# Valve_Board.net
KiCad netlist of a schematic drawn in EAGLE
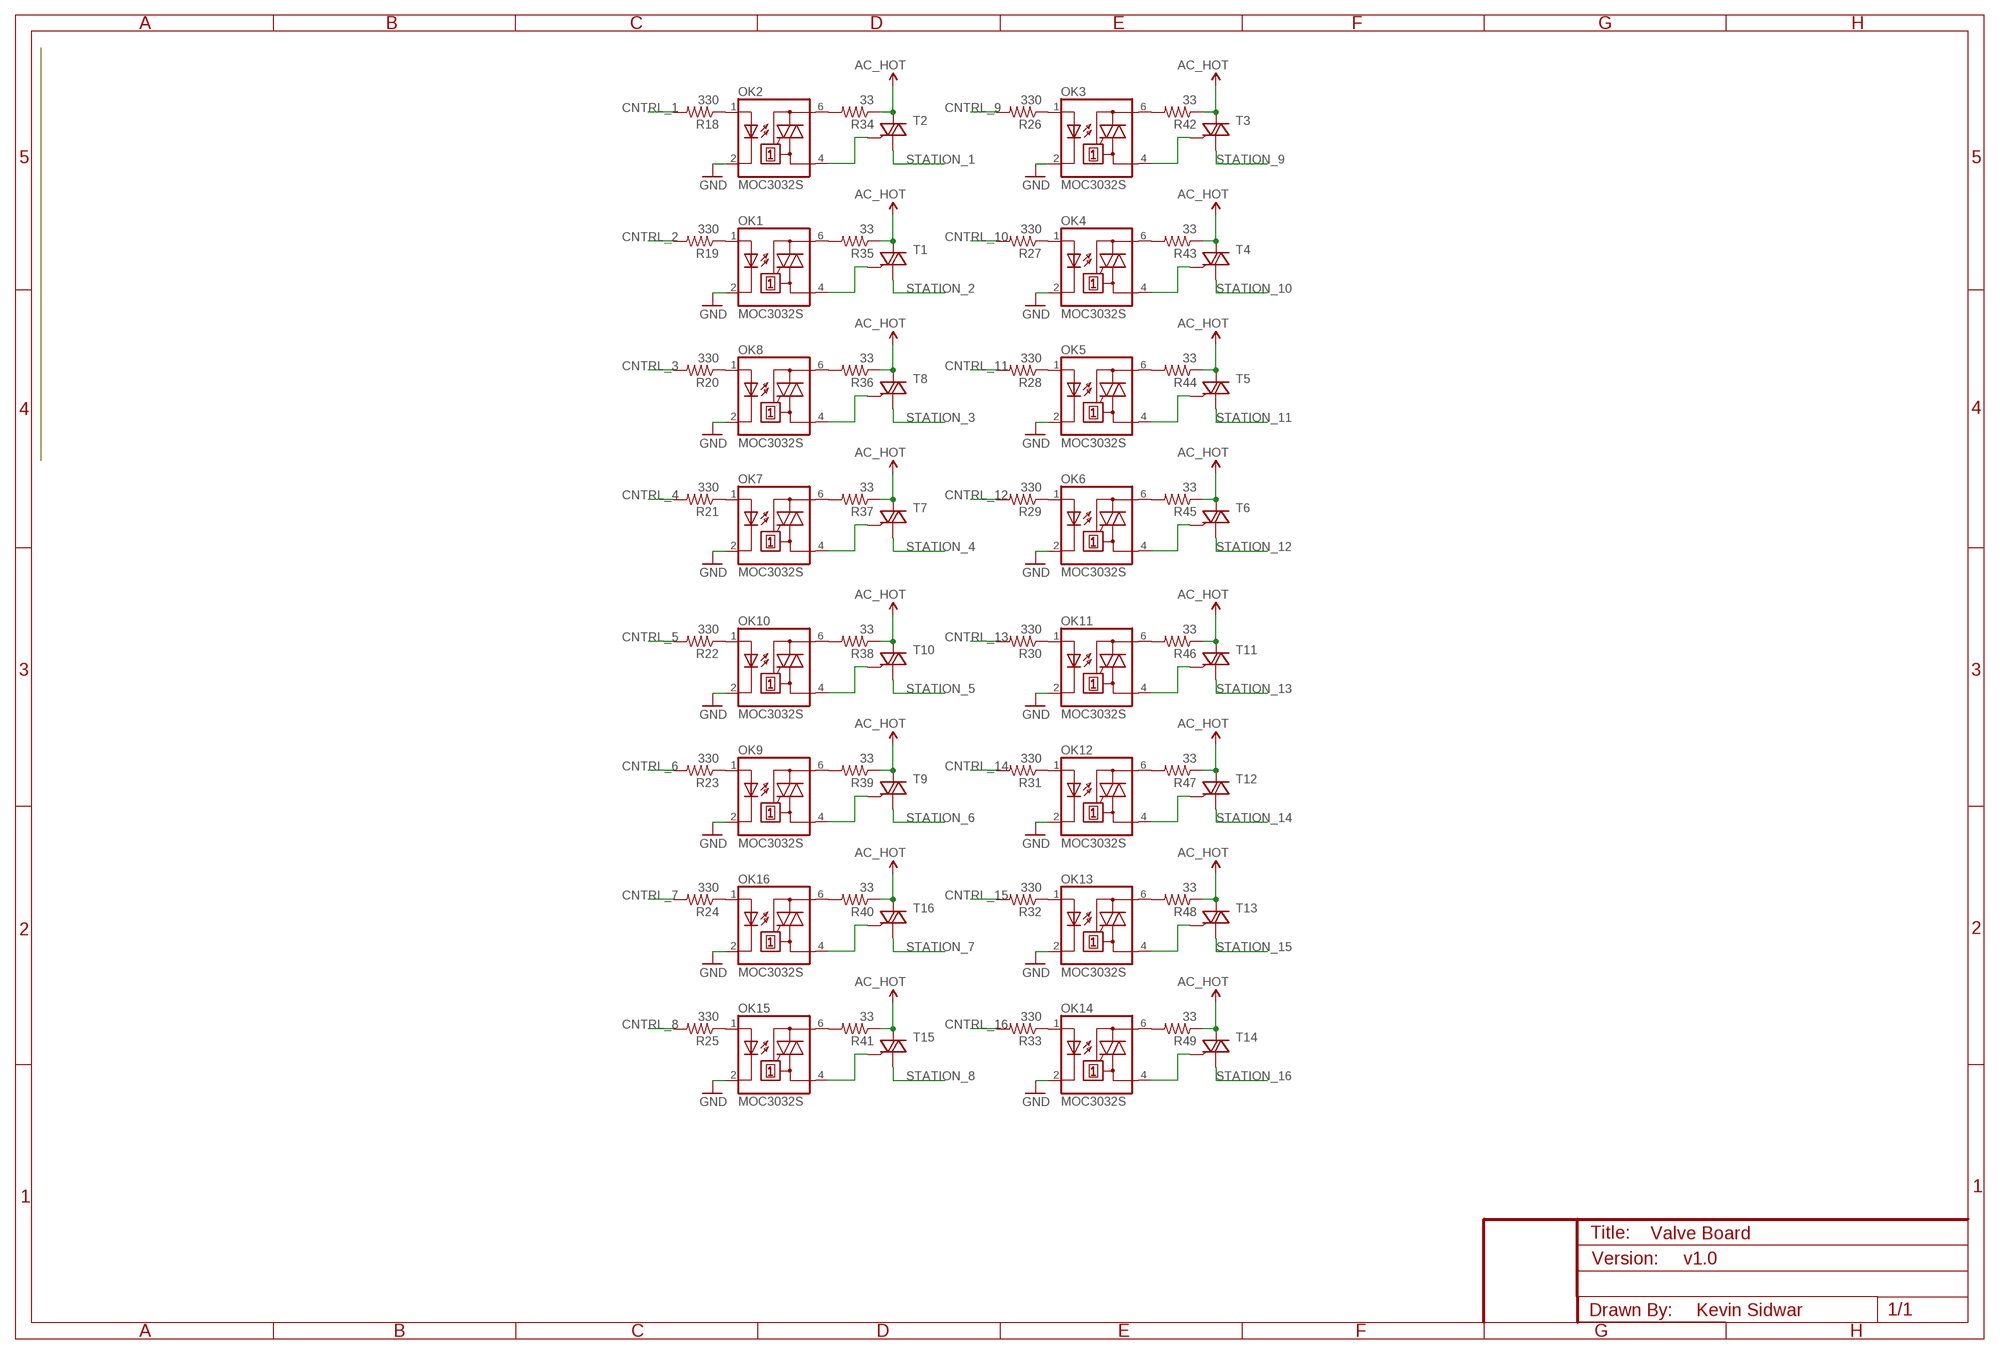
[diagram p0: schematic, sheet 1]

(export (version "E")
  (design (tool "Eeschema 10.0.6"))
  (components
    (comp (ref "OK1")
      (value "MOC3032S")
      (footprint "eagle-import:DIL6-SMD")
      (fields (field (name "MF") "FAIRCHILD SEMICONDUCTOR") (field (name "MPN") "MOC3032S-M"))
      (libsource (lib "eagle-import") (part "MOC30S32"))
    )
    (comp (ref "OK2")
      (value "MOC3032S")
      (footprint "eagle-import:DIL6-SMD")
      (fields (field (name "MF") "FAIRCHILD SEMICONDUCTOR") (field (name "MPN") "MOC3032S-M"))
      (libsource (lib "eagle-import") (part "MOC30S32"))
    )
    (comp (ref "OK3")
      (value "MOC3032S")
      (footprint "eagle-import:DIL6-SMD")
      (fields (field (name "MF") "FAIRCHILD SEMICONDUCTOR") (field (name "MPN") "MOC3032S-M"))
      (libsource (lib "eagle-import") (part "MOC30S32"))
    )
    (comp (ref "OK4")
      (value "MOC3032S")
      (footprint "eagle-import:DIL6-SMD")
      (fields (field (name "MF") "FAIRCHILD SEMICONDUCTOR") (field (name "MPN") "MOC3032S-M"))
      (libsource (lib "eagle-import") (part "MOC30S32"))
    )
    (comp (ref "OK5")
      (value "MOC3032S")
      (footprint "eagle-import:DIL6-SMD")
      (fields (field (name "MF") "FAIRCHILD SEMICONDUCTOR") (field (name "MPN") "MOC3032S-M"))
      (libsource (lib "eagle-import") (part "MOC30S32"))
    )
    (comp (ref "OK6")
      (value "MOC3032S")
      (footprint "eagle-import:DIL6-SMD")
      (fields (field (name "MF") "FAIRCHILD SEMICONDUCTOR") (field (name "MPN") "MOC3032S-M"))
      (libsource (lib "eagle-import") (part "MOC30S32"))
    )
    (comp (ref "OK7")
      (value "MOC3032S")
      (footprint "eagle-import:DIL6-SMD")
      (fields (field (name "MF") "FAIRCHILD SEMICONDUCTOR") (field (name "MPN") "MOC3032S-M"))
      (libsource (lib "eagle-import") (part "MOC30S32"))
    )
    (comp (ref "OK8")
      (value "MOC3032S")
      (footprint "eagle-import:DIL6-SMD")
      (fields (field (name "MF") "FAIRCHILD SEMICONDUCTOR") (field (name "MPN") "MOC3032S-M"))
      (libsource (lib "eagle-import") (part "MOC30S32"))
    )
    (comp (ref "OK9")
      (value "MOC3032S")
      (footprint "eagle-import:DIL6-SMD")
      (fields (field (name "MF") "FAIRCHILD SEMICONDUCTOR") (field (name "MPN") "MOC3032S-M"))
      (libsource (lib "eagle-import") (part "MOC30S32"))
    )
    (comp (ref "OK10")
      (value "MOC3032S")
      (footprint "eagle-import:DIL6-SMD")
      (fields (field (name "MF") "FAIRCHILD SEMICONDUCTOR") (field (name "MPN") "MOC3032S-M"))
      (libsource (lib "eagle-import") (part "MOC30S32"))
    )
    (comp (ref "OK11")
      (value "MOC3032S")
      (footprint "eagle-import:DIL6-SMD")
      (fields (field (name "MF") "FAIRCHILD SEMICONDUCTOR") (field (name "MPN") "MOC3032S-M"))
      (libsource (lib "eagle-import") (part "MOC30S32"))
    )
    (comp (ref "OK12")
      (value "MOC3032S")
      (footprint "eagle-import:DIL6-SMD")
      (fields (field (name "MF") "FAIRCHILD SEMICONDUCTOR") (field (name "MPN") "MOC3032S-M"))
      (libsource (lib "eagle-import") (part "MOC30S32"))
    )
    (comp (ref "OK13")
      (value "MOC3032S")
      (footprint "eagle-import:DIL6-SMD")
      (fields (field (name "MF") "FAIRCHILD SEMICONDUCTOR") (field (name "MPN") "MOC3032S-M"))
      (libsource (lib "eagle-import") (part "MOC30S32"))
    )
    (comp (ref "OK14")
      (value "MOC3032S")
      (footprint "eagle-import:DIL6-SMD")
      (fields (field (name "MF") "FAIRCHILD SEMICONDUCTOR") (field (name "MPN") "MOC3032S-M"))
      (libsource (lib "eagle-import") (part "MOC30S32"))
    )
    (comp (ref "OK15")
      (value "MOC3032S")
      (footprint "eagle-import:DIL6-SMD")
      (fields (field (name "MF") "FAIRCHILD SEMICONDUCTOR") (field (name "MPN") "MOC3032S-M"))
      (libsource (lib "eagle-import") (part "MOC30S32"))
    )
    (comp (ref "OK16")
      (value "MOC3032S")
      (footprint "eagle-import:DIL6-SMD")
      (fields (field (name "MF") "FAIRCHILD SEMICONDUCTOR") (field (name "MPN") "MOC3032S-M"))
      (libsource (lib "eagle-import") (part "MOC30S32"))
    )
    (comp (ref "R18")
      (value "330")
      (footprint "eagle-import:0603-RES")
      (libsource (lib "eagle-import") (part "RESISTOR0603-RES"))
    )
    (comp (ref "R19")
      (value "330")
      (footprint "eagle-import:0603-RES")
      (libsource (lib "eagle-import") (part "RESISTOR0603-RES"))
    )
    (comp (ref "R20")
      (value "330")
      (footprint "eagle-import:0603-RES")
      (libsource (lib "eagle-import") (part "RESISTOR0603-RES"))
    )
    (comp (ref "R21")
      (value "330")
      (footprint "eagle-import:0603-RES")
      (libsource (lib "eagle-import") (part "RESISTOR0603-RES"))
    )
    (comp (ref "R22")
      (value "330")
      (footprint "eagle-import:0603-RES")
      (libsource (lib "eagle-import") (part "RESISTOR0603-RES"))
    )
    (comp (ref "R23")
      (value "330")
      (footprint "eagle-import:0603-RES")
      (libsource (lib "eagle-import") (part "RESISTOR0603-RES"))
    )
    (comp (ref "R24")
      (value "330")
      (footprint "eagle-import:0603-RES")
      (libsource (lib "eagle-import") (part "RESISTOR0603-RES"))
    )
    (comp (ref "R25")
      (value "330")
      (footprint "eagle-import:0603-RES")
      (libsource (lib "eagle-import") (part "RESISTOR0603-RES"))
    )
    (comp (ref "R26")
      (value "330")
      (footprint "eagle-import:0603-RES")
      (libsource (lib "eagle-import") (part "RESISTOR0603-RES"))
    )
    (comp (ref "R27")
      (value "330")
      (footprint "eagle-import:0603-RES")
      (libsource (lib "eagle-import") (part "RESISTOR0603-RES"))
    )
    (comp (ref "R28")
      (value "330")
      (footprint "eagle-import:0603-RES")
      (libsource (lib "eagle-import") (part "RESISTOR0603-RES"))
    )
    (comp (ref "R29")
      (value "330")
      (footprint "eagle-import:0603-RES")
      (libsource (lib "eagle-import") (part "RESISTOR0603-RES"))
    )
    (comp (ref "R30")
      (value "330")
      (footprint "eagle-import:0603-RES")
      (libsource (lib "eagle-import") (part "RESISTOR0603-RES"))
    )
    (comp (ref "R31")
      (value "330")
      (footprint "eagle-import:0603-RES")
      (libsource (lib "eagle-import") (part "RESISTOR0603-RES"))
    )
    (comp (ref "R32")
      (value "330")
      (footprint "eagle-import:0603-RES")
      (libsource (lib "eagle-import") (part "RESISTOR0603-RES"))
    )
    (comp (ref "R33")
      (value "330")
      (footprint "eagle-import:0603-RES")
      (libsource (lib "eagle-import") (part "RESISTOR0603-RES"))
    )
    (comp (ref "R34")
      (value "33")
      (footprint "eagle-import:0603-RES")
      (libsource (lib "eagle-import") (part "RESISTOR0603-RES"))
    )
    (comp (ref "R35")
      (value "33")
      (footprint "eagle-import:0603-RES")
      (libsource (lib "eagle-import") (part "RESISTOR0603-RES"))
    )
    (comp (ref "R36")
      (value "33")
      (footprint "eagle-import:0603-RES")
      (libsource (lib "eagle-import") (part "RESISTOR0603-RES"))
    )
    (comp (ref "R37")
      (value "33")
      (footprint "eagle-import:0603-RES")
      (libsource (lib "eagle-import") (part "RESISTOR0603-RES"))
    )
    (comp (ref "R38")
      (value "33")
      (footprint "eagle-import:0603-RES")
      (libsource (lib "eagle-import") (part "RESISTOR0603-RES"))
    )
    (comp (ref "R39")
      (value "33")
      (footprint "eagle-import:0603-RES")
      (libsource (lib "eagle-import") (part "RESISTOR0603-RES"))
    )
    (comp (ref "R40")
      (value "33")
      (footprint "eagle-import:0603-RES")
      (libsource (lib "eagle-import") (part "RESISTOR0603-RES"))
    )
    (comp (ref "R41")
      (value "33")
      (footprint "eagle-import:0603-RES")
      (libsource (lib "eagle-import") (part "RESISTOR0603-RES"))
    )
    (comp (ref "R42")
      (value "33")
      (footprint "eagle-import:0603-RES")
      (libsource (lib "eagle-import") (part "RESISTOR0603-RES"))
    )
    (comp (ref "R43")
      (value "33")
      (footprint "eagle-import:0603-RES")
      (libsource (lib "eagle-import") (part "RESISTOR0603-RES"))
    )
    (comp (ref "R44")
      (value "33")
      (footprint "eagle-import:0603-RES")
      (libsource (lib "eagle-import") (part "RESISTOR0603-RES"))
    )
    (comp (ref "R45")
      (value "33")
      (footprint "eagle-import:0603-RES")
      (libsource (lib "eagle-import") (part "RESISTOR0603-RES"))
    )
    (comp (ref "R46")
      (value "33")
      (footprint "eagle-import:0603-RES")
      (libsource (lib "eagle-import") (part "RESISTOR0603-RES"))
    )
    (comp (ref "R47")
      (value "33")
      (footprint "eagle-import:0603-RES")
      (libsource (lib "eagle-import") (part "RESISTOR0603-RES"))
    )
    (comp (ref "R48")
      (value "33")
      (footprint "eagle-import:0603-RES")
      (libsource (lib "eagle-import") (part "RESISTOR0603-RES"))
    )
    (comp (ref "R49")
      (value "33")
      (footprint "eagle-import:0603-RES")
      (libsource (lib "eagle-import") (part "RESISTOR0603-RES"))
    )
    (comp (ref "T1")
      (value "LF-TRIACSOT223")
      (footprint "eagle-import:SOT223")
      (libsource (lib "eagle-import") (part "LF-TRIACSOT223"))
    )
    (comp (ref "T2")
      (value "LF-TRIACSOT223")
      (footprint "eagle-import:SOT223")
      (libsource (lib "eagle-import") (part "LF-TRIACSOT223"))
    )
    (comp (ref "T3")
      (value "LF-TRIACSOT223")
      (footprint "eagle-import:SOT223")
      (libsource (lib "eagle-import") (part "LF-TRIACSOT223"))
    )
    (comp (ref "T4")
      (value "LF-TRIACSOT223")
      (footprint "eagle-import:SOT223")
      (libsource (lib "eagle-import") (part "LF-TRIACSOT223"))
    )
    (comp (ref "T5")
      (value "LF-TRIACSOT223")
      (footprint "eagle-import:SOT223")
      (libsource (lib "eagle-import") (part "LF-TRIACSOT223"))
    )
    (comp (ref "T6")
      (value "LF-TRIACSOT223")
      (footprint "eagle-import:SOT223")
      (libsource (lib "eagle-import") (part "LF-TRIACSOT223"))
    )
    (comp (ref "T7")
      (value "LF-TRIACSOT223")
      (footprint "eagle-import:SOT223")
      (libsource (lib "eagle-import") (part "LF-TRIACSOT223"))
    )
    (comp (ref "T8")
      (value "LF-TRIACSOT223")
      (footprint "eagle-import:SOT223")
      (libsource (lib "eagle-import") (part "LF-TRIACSOT223"))
    )
    (comp (ref "T9")
      (value "LF-TRIACSOT223")
      (footprint "eagle-import:SOT223")
      (libsource (lib "eagle-import") (part "LF-TRIACSOT223"))
    )
    (comp (ref "T10")
      (value "LF-TRIACSOT223")
      (footprint "eagle-import:SOT223")
      (libsource (lib "eagle-import") (part "LF-TRIACSOT223"))
    )
    (comp (ref "T11")
      (value "LF-TRIACSOT223")
      (footprint "eagle-import:SOT223")
      (libsource (lib "eagle-import") (part "LF-TRIACSOT223"))
    )
    (comp (ref "T12")
      (value "LF-TRIACSOT223")
      (footprint "eagle-import:SOT223")
      (libsource (lib "eagle-import") (part "LF-TRIACSOT223"))
    )
    (comp (ref "T13")
      (value "LF-TRIACSOT223")
      (footprint "eagle-import:SOT223")
      (libsource (lib "eagle-import") (part "LF-TRIACSOT223"))
    )
    (comp (ref "T14")
      (value "LF-TRIACSOT223")
      (footprint "eagle-import:SOT223")
      (libsource (lib "eagle-import") (part "LF-TRIACSOT223"))
    )
    (comp (ref "T15")
      (value "LF-TRIACSOT223")
      (footprint "eagle-import:SOT223")
      (libsource (lib "eagle-import") (part "LF-TRIACSOT223"))
    )
    (comp (ref "T16")
      (value "LF-TRIACSOT223")
      (footprint "eagle-import:SOT223")
      (libsource (lib "eagle-import") (part "LF-TRIACSOT223"))
    )
  )
  (nets
    (net (code "1") (name "/CNTRL_1") (class "Default")
      (node (ref "R18") (pin "2") (pinfunction "2_2") (pintype "passive"))
    )
    (net (code "2") (name "/CNTRL_2") (class "Default")
      (node (ref "R19") (pin "2") (pinfunction "2_2") (pintype "passive"))
    )
    (net (code "3") (name "/CNTRL_3") (class "Default")
      (node (ref "R20") (pin "2") (pinfunction "2_2") (pintype "passive"))
    )
    (net (code "4") (name "/CNTRL_4") (class "Default")
      (node (ref "R21") (pin "2") (pinfunction "2_2") (pintype "passive"))
    )
    (net (code "5") (name "/CNTRL_5") (class "Default")
      (node (ref "R22") (pin "2") (pinfunction "2_2") (pintype "passive"))
    )
    (net (code "6") (name "/CNTRL_6") (class "Default")
      (node (ref "R23") (pin "2") (pinfunction "2_2") (pintype "passive"))
    )
    (net (code "7") (name "/CNTRL_7") (class "Default")
      (node (ref "R24") (pin "2") (pinfunction "2_2") (pintype "passive"))
    )
    (net (code "8") (name "/CNTRL_8") (class "Default")
      (node (ref "R25") (pin "2") (pinfunction "2_2") (pintype "passive"))
    )
    (net (code "9") (name "/CNTRL_9") (class "Default")
      (node (ref "R26") (pin "2") (pinfunction "2_2") (pintype "passive"))
    )
    (net (code "10") (name "/CNTRL_10") (class "Default")
      (node (ref "R27") (pin "2") (pinfunction "2_2") (pintype "passive"))
    )
    (net (code "11") (name "/CNTRL_11") (class "Default")
      (node (ref "R28") (pin "2") (pinfunction "2_2") (pintype "passive"))
    )
    (net (code "12") (name "/CNTRL_12") (class "Default")
      (node (ref "R29") (pin "2") (pinfunction "2_2") (pintype "passive"))
    )
    (net (code "13") (name "/CNTRL_13") (class "Default")
      (node (ref "R30") (pin "2") (pinfunction "2_2") (pintype "passive"))
    )
    (net (code "14") (name "/CNTRL_14") (class "Default")
      (node (ref "R31") (pin "2") (pinfunction "2_2") (pintype "passive"))
    )
    (net (code "15") (name "/CNTRL_15") (class "Default")
      (node (ref "R32") (pin "2") (pinfunction "2_2") (pintype "passive"))
    )
    (net (code "16") (name "/CNTRL_16") (class "Default")
      (node (ref "R33") (pin "2") (pinfunction "2_2") (pintype "passive"))
    )
    (net (code "17") (name "/STATION_1") (class "Default")
      (node (ref "T2") (pin "1") (pinfunction "A1_1") (pintype "passive"))
    )
    (net (code "18") (name "/STATION_2") (class "Default")
      (node (ref "T1") (pin "1") (pinfunction "A1_1") (pintype "passive"))
    )
    (net (code "19") (name "/STATION_3") (class "Default")
      (node (ref "T8") (pin "1") (pinfunction "A1_1") (pintype "passive"))
    )
    (net (code "20") (name "/STATION_4") (class "Default")
      (node (ref "T7") (pin "1") (pinfunction "A1_1") (pintype "passive"))
    )
    (net (code "21") (name "/STATION_5") (class "Default")
      (node (ref "T10") (pin "1") (pinfunction "A1_1") (pintype "passive"))
    )
    (net (code "22") (name "/STATION_6") (class "Default")
      (node (ref "T9") (pin "1") (pinfunction "A1_1") (pintype "passive"))
    )
    (net (code "23") (name "/STATION_7") (class "Default")
      (node (ref "T16") (pin "1") (pinfunction "A1_1") (pintype "passive"))
    )
    (net (code "24") (name "/STATION_8") (class "Default")
      (node (ref "T15") (pin "1") (pinfunction "A1_1") (pintype "passive"))
    )
    (net (code "25") (name "/STATION_9") (class "Default")
      (node (ref "T3") (pin "1") (pinfunction "A1_1") (pintype "passive"))
    )
    (net (code "26") (name "/STATION_10") (class "Default")
      (node (ref "T4") (pin "1") (pinfunction "A1_1") (pintype "passive"))
    )
    (net (code "27") (name "/STATION_11") (class "Default")
      (node (ref "T5") (pin "1") (pinfunction "A1_1") (pintype "passive"))
    )
    (net (code "28") (name "/STATION_12") (class "Default")
      (node (ref "T6") (pin "1") (pinfunction "A1_1") (pintype "passive"))
    )
    (net (code "29") (name "/STATION_13") (class "Default")
      (node (ref "T11") (pin "1") (pinfunction "A1_1") (pintype "passive"))
    )
    (net (code "30") (name "/STATION_14") (class "Default")
      (node (ref "T12") (pin "1") (pinfunction "A1_1") (pintype "passive"))
    )
    (net (code "31") (name "/STATION_15") (class "Default")
      (node (ref "T13") (pin "1") (pinfunction "A1_1") (pintype "passive"))
    )
    (net (code "32") (name "/STATION_16") (class "Default")
      (node (ref "T14") (pin "1") (pinfunction "A1_1") (pintype "passive"))
    )
    (net (code "33") (name "AC_HOT") (class "Default")
      (node (ref "R34") (pin "1") (pinfunction "1_1") (pintype "passive"))
      (node (ref "R35") (pin "1") (pinfunction "1_1") (pintype "passive"))
      (node (ref "R36") (pin "1") (pinfunction "1_1") (pintype "passive"))
      (node (ref "R37") (pin "1") (pinfunction "1_1") (pintype "passive"))
      (node (ref "R38") (pin "1") (pinfunction "1_1") (pintype "passive"))
      (node (ref "R39") (pin "1") (pinfunction "1_1") (pintype "passive"))
      (node (ref "R40") (pin "1") (pinfunction "1_1") (pintype "passive"))
      (node (ref "R41") (pin "1") (pinfunction "1_1") (pintype "passive"))
      (node (ref "R42") (pin "1") (pinfunction "1_1") (pintype "passive"))
      (node (ref "R43") (pin "1") (pinfunction "1_1") (pintype "passive"))
      (node (ref "R44") (pin "1") (pinfunction "1_1") (pintype "passive"))
      (node (ref "R45") (pin "1") (pinfunction "1_1") (pintype "passive"))
      (node (ref "R46") (pin "1") (pinfunction "1_1") (pintype "passive"))
      (node (ref "R47") (pin "1") (pinfunction "1_1") (pintype "passive"))
      (node (ref "R48") (pin "1") (pinfunction "1_1") (pintype "passive"))
      (node (ref "R49") (pin "1") (pinfunction "1_1") (pintype "passive"))
      (node (ref "T1") (pin "2") (pinfunction "A2_2") (pintype "passive"))
      (node (ref "T10") (pin "2") (pinfunction "A2_2") (pintype "passive"))
      (node (ref "T11") (pin "2") (pinfunction "A2_2") (pintype "passive"))
      (node (ref "T12") (pin "2") (pinfunction "A2_2") (pintype "passive"))
      (node (ref "T13") (pin "2") (pinfunction "A2_2") (pintype "passive"))
      (node (ref "T14") (pin "2") (pinfunction "A2_2") (pintype "passive"))
      (node (ref "T15") (pin "2") (pinfunction "A2_2") (pintype "passive"))
      (node (ref "T16") (pin "2") (pinfunction "A2_2") (pintype "passive"))
      (node (ref "T2") (pin "2") (pinfunction "A2_2") (pintype "passive"))
      (node (ref "T3") (pin "2") (pinfunction "A2_2") (pintype "passive"))
      (node (ref "T4") (pin "2") (pinfunction "A2_2") (pintype "passive"))
      (node (ref "T5") (pin "2") (pinfunction "A2_2") (pintype "passive"))
      (node (ref "T6") (pin "2") (pinfunction "A2_2") (pintype "passive"))
      (node (ref "T7") (pin "2") (pinfunction "A2_2") (pintype "passive"))
      (node (ref "T8") (pin "2") (pinfunction "A2_2") (pintype "passive"))
      (node (ref "T9") (pin "2") (pinfunction "A2_2") (pintype "passive"))
    )
    (net (code "34") (name "GND") (class "Default")
      (node (ref "OK1") (pin "2") (pinfunction "C_2") (pintype "passive"))
      (node (ref "OK10") (pin "2") (pinfunction "C_2") (pintype "passive"))
      (node (ref "OK11") (pin "2") (pinfunction "C_2") (pintype "passive"))
      (node (ref "OK12") (pin "2") (pinfunction "C_2") (pintype "passive"))
      (node (ref "OK13") (pin "2") (pinfunction "C_2") (pintype "passive"))
      (node (ref "OK14") (pin "2") (pinfunction "C_2") (pintype "passive"))
      (node (ref "OK15") (pin "2") (pinfunction "C_2") (pintype "passive"))
      (node (ref "OK16") (pin "2") (pinfunction "C_2") (pintype "passive"))
      (node (ref "OK2") (pin "2") (pinfunction "C_2") (pintype "passive"))
      (node (ref "OK3") (pin "2") (pinfunction "C_2") (pintype "passive"))
      (node (ref "OK4") (pin "2") (pinfunction "C_2") (pintype "passive"))
      (node (ref "OK5") (pin "2") (pinfunction "C_2") (pintype "passive"))
      (node (ref "OK6") (pin "2") (pinfunction "C_2") (pintype "passive"))
      (node (ref "OK7") (pin "2") (pinfunction "C_2") (pintype "passive"))
      (node (ref "OK8") (pin "2") (pinfunction "C_2") (pintype "passive"))
      (node (ref "OK9") (pin "2") (pinfunction "C_2") (pintype "passive"))
    )
    (net (code "35") (name "Net-(OK1-A)") (class "Default")
      (node (ref "OK1") (pin "1") (pinfunction "A_1") (pintype "passive"))
      (node (ref "R19") (pin "1") (pinfunction "1_1") (pintype "passive"))
    )
    (net (code "36") (name "Net-(OK1-A1)") (class "Default")
      (node (ref "OK1") (pin "4") (pinfunction "A1_4") (pintype "passive"))
      (node (ref "T1") (pin "3") (pinfunction "G_3") (pintype "passive"))
    )
    (net (code "37") (name "Net-(OK1-A2)") (class "Default")
      (node (ref "OK1") (pin "6") (pinfunction "A2_6") (pintype "passive"))
      (node (ref "R35") (pin "2") (pinfunction "2_2") (pintype "passive"))
    )
    (net (code "38") (name "Net-(OK2-A)") (class "Default")
      (node (ref "OK2") (pin "1") (pinfunction "A_1") (pintype "passive"))
      (node (ref "R18") (pin "1") (pinfunction "1_1") (pintype "passive"))
    )
    (net (code "39") (name "Net-(OK2-A1)") (class "Default")
      (node (ref "OK2") (pin "4") (pinfunction "A1_4") (pintype "passive"))
      (node (ref "T2") (pin "3") (pinfunction "G_3") (pintype "passive"))
    )
    (net (code "40") (name "Net-(OK2-A2)") (class "Default")
      (node (ref "OK2") (pin "6") (pinfunction "A2_6") (pintype "passive"))
      (node (ref "R34") (pin "2") (pinfunction "2_2") (pintype "passive"))
    )
    (net (code "41") (name "Net-(OK3-A)") (class "Default")
      (node (ref "OK3") (pin "1") (pinfunction "A_1") (pintype "passive"))
      (node (ref "R26") (pin "1") (pinfunction "1_1") (pintype "passive"))
    )
    (net (code "42") (name "Net-(OK3-A1)") (class "Default")
      (node (ref "OK3") (pin "4") (pinfunction "A1_4") (pintype "passive"))
      (node (ref "T3") (pin "3") (pinfunction "G_3") (pintype "passive"))
    )
    (net (code "43") (name "Net-(OK3-A2)") (class "Default")
      (node (ref "OK3") (pin "6") (pinfunction "A2_6") (pintype "passive"))
      (node (ref "R42") (pin "2") (pinfunction "2_2") (pintype "passive"))
    )
    (net (code "44") (name "Net-(OK4-A)") (class "Default")
      (node (ref "OK4") (pin "1") (pinfunction "A_1") (pintype "passive"))
      (node (ref "R27") (pin "1") (pinfunction "1_1") (pintype "passive"))
    )
    (net (code "45") (name "Net-(OK4-A1)") (class "Default")
      (node (ref "OK4") (pin "4") (pinfunction "A1_4") (pintype "passive"))
      (node (ref "T4") (pin "3") (pinfunction "G_3") (pintype "passive"))
    )
    (net (code "46") (name "Net-(OK4-A2)") (class "Default")
      (node (ref "OK4") (pin "6") (pinfunction "A2_6") (pintype "passive"))
      (node (ref "R43") (pin "2") (pinfunction "2_2") (pintype "passive"))
    )
    (net (code "47") (name "Net-(OK5-A)") (class "Default")
      (node (ref "OK5") (pin "1") (pinfunction "A_1") (pintype "passive"))
      (node (ref "R28") (pin "1") (pinfunction "1_1") (pintype "passive"))
    )
    (net (code "48") (name "Net-(OK5-A1)") (class "Default")
      (node (ref "OK5") (pin "4") (pinfunction "A1_4") (pintype "passive"))
      (node (ref "T5") (pin "3") (pinfunction "G_3") (pintype "passive"))
    )
    (net (code "49") (name "Net-(OK5-A2)") (class "Default")
      (node (ref "OK5") (pin "6") (pinfunction "A2_6") (pintype "passive"))
      (node (ref "R44") (pin "2") (pinfunction "2_2") (pintype "passive"))
    )
    (net (code "50") (name "Net-(OK6-A)") (class "Default")
      (node (ref "OK6") (pin "1") (pinfunction "A_1") (pintype "passive"))
      (node (ref "R29") (pin "1") (pinfunction "1_1") (pintype "passive"))
    )
    (net (code "51") (name "Net-(OK6-A1)") (class "Default")
      (node (ref "OK6") (pin "4") (pinfunction "A1_4") (pintype "passive"))
      (node (ref "T6") (pin "3") (pinfunction "G_3") (pintype "passive"))
    )
    (net (code "52") (name "Net-(OK6-A2)") (class "Default")
      (node (ref "OK6") (pin "6") (pinfunction "A2_6") (pintype "passive"))
      (node (ref "R45") (pin "2") (pinfunction "2_2") (pintype "passive"))
    )
    (net (code "53") (name "Net-(OK7-A)") (class "Default")
      (node (ref "OK7") (pin "1") (pinfunction "A_1") (pintype "passive"))
      (node (ref "R21") (pin "1") (pinfunction "1_1") (pintype "passive"))
    )
    (net (code "54") (name "Net-(OK7-A1)") (class "Default")
      (node (ref "OK7") (pin "4") (pinfunction "A1_4") (pintype "passive"))
      (node (ref "T7") (pin "3") (pinfunction "G_3") (pintype "passive"))
    )
    (net (code "55") (name "Net-(OK7-A2)") (class "Default")
      (node (ref "OK7") (pin "6") (pinfunction "A2_6") (pintype "passive"))
      (node (ref "R37") (pin "2") (pinfunction "2_2") (pintype "passive"))
    )
    (net (code "56") (name "Net-(OK8-A)") (class "Default")
      (node (ref "OK8") (pin "1") (pinfunction "A_1") (pintype "passive"))
      (node (ref "R20") (pin "1") (pinfunction "1_1") (pintype "passive"))
    )
    (net (code "57") (name "Net-(OK8-A1)") (class "Default")
      (node (ref "OK8") (pin "4") (pinfunction "A1_4") (pintype "passive"))
      (node (ref "T8") (pin "3") (pinfunction "G_3") (pintype "passive"))
    )
    (net (code "58") (name "Net-(OK8-A2)") (class "Default")
      (node (ref "OK8") (pin "6") (pinfunction "A2_6") (pintype "passive"))
      (node (ref "R36") (pin "2") (pinfunction "2_2") (pintype "passive"))
    )
    (net (code "59") (name "Net-(OK9-A)") (class "Default")
      (node (ref "OK9") (pin "1") (pinfunction "A_1") (pintype "passive"))
      (node (ref "R23") (pin "1") (pinfunction "1_1") (pintype "passive"))
    )
    (net (code "60") (name "Net-(OK9-A1)") (class "Default")
      (node (ref "OK9") (pin "4") (pinfunction "A1_4") (pintype "passive"))
      (node (ref "T9") (pin "3") (pinfunction "G_3") (pintype "passive"))
    )
    (net (code "61") (name "Net-(OK9-A2)") (class "Default")
      (node (ref "OK9") (pin "6") (pinfunction "A2_6") (pintype "passive"))
      (node (ref "R39") (pin "2") (pinfunction "2_2") (pintype "passive"))
    )
    (net (code "62") (name "Net-(OK10-A)") (class "Default")
      (node (ref "OK10") (pin "1") (pinfunction "A_1") (pintype "passive"))
      (node (ref "R22") (pin "1") (pinfunction "1_1") (pintype "passive"))
    )
    (net (code "63") (name "Net-(OK10-A1)") (class "Default")
      (node (ref "OK10") (pin "4") (pinfunction "A1_4") (pintype "passive"))
      (node (ref "T10") (pin "3") (pinfunction "G_3") (pintype "passive"))
    )
    (net (code "64") (name "Net-(OK10-A2)") (class "Default")
      (node (ref "OK10") (pin "6") (pinfunction "A2_6") (pintype "passive"))
      (node (ref "R38") (pin "2") (pinfunction "2_2") (pintype "passive"))
    )
    (net (code "65") (name "Net-(OK11-A)") (class "Default")
      (node (ref "OK11") (pin "1") (pinfunction "A_1") (pintype "passive"))
      (node (ref "R30") (pin "1") (pinfunction "1_1") (pintype "passive"))
    )
    (net (code "66") (name "Net-(OK11-A1)") (class "Default")
      (node (ref "OK11") (pin "4") (pinfunction "A1_4") (pintype "passive"))
      (node (ref "T11") (pin "3") (pinfunction "G_3") (pintype "passive"))
    )
    (net (code "67") (name "Net-(OK11-A2)") (class "Default")
      (node (ref "OK11") (pin "6") (pinfunction "A2_6") (pintype "passive"))
      (node (ref "R46") (pin "2") (pinfunction "2_2") (pintype "passive"))
    )
    (net (code "68") (name "Net-(OK12-A)") (class "Default")
      (node (ref "OK12") (pin "1") (pinfunction "A_1") (pintype "passive"))
      (node (ref "R31") (pin "1") (pinfunction "1_1") (pintype "passive"))
    )
    (net (code "69") (name "Net-(OK12-A1)") (class "Default")
      (node (ref "OK12") (pin "4") (pinfunction "A1_4") (pintype "passive"))
      (node (ref "T12") (pin "3") (pinfunction "G_3") (pintype "passive"))
    )
    (net (code "70") (name "Net-(OK12-A2)") (class "Default")
      (node (ref "OK12") (pin "6") (pinfunction "A2_6") (pintype "passive"))
      (node (ref "R47") (pin "2") (pinfunction "2_2") (pintype "passive"))
    )
    (net (code "71") (name "Net-(OK13-A)") (class "Default")
      (node (ref "OK13") (pin "1") (pinfunction "A_1") (pintype "passive"))
      (node (ref "R32") (pin "1") (pinfunction "1_1") (pintype "passive"))
    )
    (net (code "72") (name "Net-(OK13-A1)") (class "Default")
      (node (ref "OK13") (pin "4") (pinfunction "A1_4") (pintype "passive"))
      (node (ref "T13") (pin "3") (pinfunction "G_3") (pintype "passive"))
    )
    (net (code "73") (name "Net-(OK13-A2)") (class "Default")
      (node (ref "OK13") (pin "6") (pinfunction "A2_6") (pintype "passive"))
      (node (ref "R48") (pin "2") (pinfunction "2_2") (pintype "passive"))
    )
    (net (code "74") (name "Net-(OK14-A)") (class "Default")
      (node (ref "OK14") (pin "1") (pinfunction "A_1") (pintype "passive"))
      (node (ref "R33") (pin "1") (pinfunction "1_1") (pintype "passive"))
    )
    (net (code "75") (name "Net-(OK14-A1)") (class "Default")
      (node (ref "OK14") (pin "4") (pinfunction "A1_4") (pintype "passive"))
      (node (ref "T14") (pin "3") (pinfunction "G_3") (pintype "passive"))
    )
    (net (code "76") (name "Net-(OK14-A2)") (class "Default")
      (node (ref "OK14") (pin "6") (pinfunction "A2_6") (pintype "passive"))
      (node (ref "R49") (pin "2") (pinfunction "2_2") (pintype "passive"))
    )
    (net (code "77") (name "Net-(OK15-A)") (class "Default")
      (node (ref "OK15") (pin "1") (pinfunction "A_1") (pintype "passive"))
      (node (ref "R25") (pin "1") (pinfunction "1_1") (pintype "passive"))
    )
    (net (code "78") (name "Net-(OK15-A1)") (class "Default")
      (node (ref "OK15") (pin "4") (pinfunction "A1_4") (pintype "passive"))
      (node (ref "T15") (pin "3") (pinfunction "G_3") (pintype "passive"))
    )
    (net (code "79") (name "Net-(OK15-A2)") (class "Default")
      (node (ref "OK15") (pin "6") (pinfunction "A2_6") (pintype "passive"))
      (node (ref "R41") (pin "2") (pinfunction "2_2") (pintype "passive"))
    )
    (net (code "80") (name "Net-(OK16-A)") (class "Default")
      (node (ref "OK16") (pin "1") (pinfunction "A_1") (pintype "passive"))
      (node (ref "R24") (pin "1") (pinfunction "1_1") (pintype "passive"))
    )
    (net (code "81") (name "Net-(OK16-A1)") (class "Default")
      (node (ref "OK16") (pin "4") (pinfunction "A1_4") (pintype "passive"))
      (node (ref "T16") (pin "3") (pinfunction "G_3") (pintype "passive"))
    )
    (net (code "82") (name "Net-(OK16-A2)") (class "Default")
      (node (ref "OK16") (pin "6") (pinfunction "A2_6") (pintype "passive"))
      (node (ref "R40") (pin "2") (pinfunction "2_2") (pintype "passive"))
    )
  )
)
